# PCB_teensy.net
KiCad netlist of a schematic drawn in EAGLE
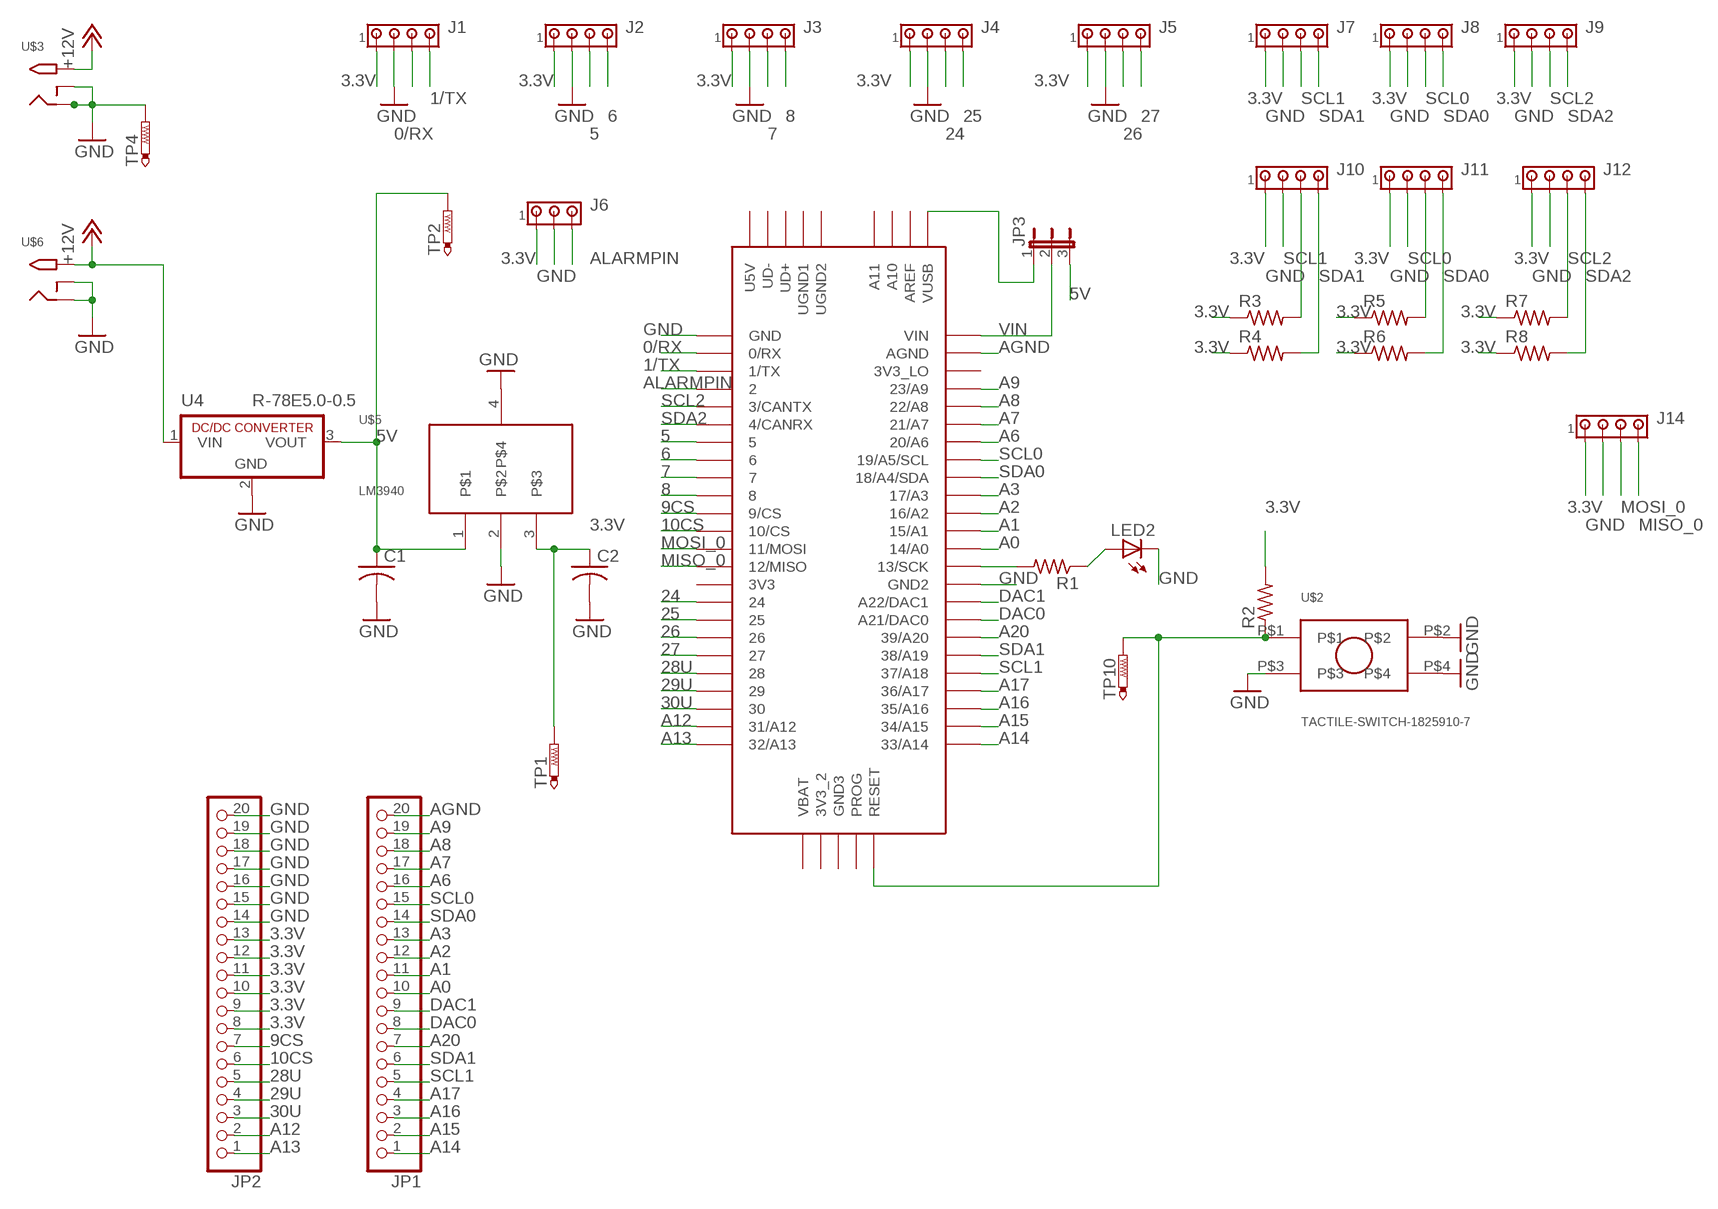
[diagram p0: schematic, sheet 1]

(export (version "E")
  (design (tool "Eeschema 10.0.6"))
  (components
    (comp (ref "C1")
      (value "C-USC0805")
      (footprint "eagle-import:C0805")
      (libsource (lib "eagle-import") (part "C-USC0805"))
    )
    (comp (ref "C2")
      (value "C-USC0805")
      (footprint "eagle-import:C0805")
      (libsource (lib "eagle-import") (part "C-USC0805"))
    )
    (comp (ref "J1")
      (value "MTA04-100")
      (footprint "eagle-import:10X04MTA")
      (libsource (lib "eagle-import") (part "MTA04-100"))
    )
    (comp (ref "J2")
      (value "MTA04-100")
      (footprint "eagle-import:10X04MTA")
      (libsource (lib "eagle-import") (part "MTA04-100"))
    )
    (comp (ref "J3")
      (value "MTA04-100")
      (footprint "eagle-import:10X04MTA")
      (libsource (lib "eagle-import") (part "MTA04-100"))
    )
    (comp (ref "J4")
      (value "MTA04-100")
      (footprint "eagle-import:10X04MTA")
      (libsource (lib "eagle-import") (part "MTA04-100"))
    )
    (comp (ref "J5")
      (value "MTA04-100")
      (footprint "eagle-import:10X04MTA")
      (libsource (lib "eagle-import") (part "MTA04-100"))
    )
    (comp (ref "J6")
      (value "MTA03-100")
      (footprint "eagle-import:10X03MTA")
      (libsource (lib "eagle-import") (part "MTA03-100"))
    )
    (comp (ref "J7")
      (value "MTA04-100")
      (footprint "eagle-import:10X04MTA")
      (libsource (lib "eagle-import") (part "MTA04-100"))
    )
    (comp (ref "J8")
      (value "MTA04-100")
      (footprint "eagle-import:10X04MTA")
      (libsource (lib "eagle-import") (part "MTA04-100"))
    )
    (comp (ref "J9")
      (value "MTA04-100")
      (footprint "eagle-import:10X04MTA")
      (libsource (lib "eagle-import") (part "MTA04-100"))
    )
    (comp (ref "J10")
      (value "MTA04-100")
      (footprint "eagle-import:10X04MTA")
      (libsource (lib "eagle-import") (part "MTA04-100"))
    )
    (comp (ref "J11")
      (value "MTA04-100")
      (footprint "eagle-import:10X04MTA")
      (libsource (lib "eagle-import") (part "MTA04-100"))
    )
    (comp (ref "J12")
      (value "MTA04-100")
      (footprint "eagle-import:10X04MTA")
      (libsource (lib "eagle-import") (part "MTA04-100"))
    )
    (comp (ref "J14")
      (value "MTA04-100")
      (footprint "eagle-import:10X04MTA")
      (libsource (lib "eagle-import") (part "MTA04-100"))
    )
    (comp (ref "JP1")
      (value "PINHD-1X20")
      (footprint "eagle-import:1X20")
      (libsource (lib "eagle-import") (part "PINHD-1X20"))
    )
    (comp (ref "JP2")
      (value "PINHD-1X20")
      (footprint "eagle-import:1X20")
      (libsource (lib "eagle-import") (part "PINHD-1X20"))
    )
    (comp (ref "JP3")
      (value "JP2W")
      (footprint "eagle-import:JP2W")
      (libsource (lib "eagle-import") (part "JP2W"))
    )
    (comp (ref "LED2")
      (value "LEDCHIP-LED0805")
      (footprint "eagle-import:CHIP-LED0805")
      (libsource (lib "eagle-import") (part "LEDCHIP-LED0805"))
    )
    (comp (ref "R1")
      (value "R-US_R0805")
      (footprint "eagle-import:R0805")
      (libsource (lib "eagle-import") (part "R-US_R0805"))
    )
    (comp (ref "R2")
      (value "R-US_R0805")
      (footprint "eagle-import:R0805")
      (libsource (lib "eagle-import") (part "R-US_R0805"))
    )
    (comp (ref "R3")
      (value "R-US_R0805")
      (footprint "eagle-import:R0805")
      (libsource (lib "eagle-import") (part "R-US_R0805"))
    )
    (comp (ref "R4")
      (value "R-US_R0805")
      (footprint "eagle-import:R0805")
      (libsource (lib "eagle-import") (part "R-US_R0805"))
    )
    (comp (ref "R5")
      (value "R-US_R0805")
      (footprint "eagle-import:R0805")
      (libsource (lib "eagle-import") (part "R-US_R0805"))
    )
    (comp (ref "R6")
      (value "R-US_R0805")
      (footprint "eagle-import:R0805")
      (libsource (lib "eagle-import") (part "R-US_R0805"))
    )
    (comp (ref "R7")
      (value "R-US_R0805")
      (footprint "eagle-import:R0805")
      (libsource (lib "eagle-import") (part "R-US_R0805"))
    )
    (comp (ref "R8")
      (value "R-US_R0805")
      (footprint "eagle-import:R0805")
      (libsource (lib "eagle-import") (part "R-US_R0805"))
    )
    (comp (ref "TP1")
      (value "PTR1B2,54")
      (footprint "eagle-import:B2,54")
      (libsource (lib "eagle-import") (part "PTR1B2,54"))
    )
    (comp (ref "TP2")
      (value "PTR1B2,54")
      (footprint "eagle-import:B2,54")
      (libsource (lib "eagle-import") (part "PTR1B2,54"))
    )
    (comp (ref "TP4")
      (value "PTR1B2,54")
      (footprint "eagle-import:B2,54")
      (libsource (lib "eagle-import") (part "PTR1B2,54"))
    )
    (comp (ref "TP10")
      (value "PTR1B2,54")
      (footprint "eagle-import:B2,54")
      (libsource (lib "eagle-import") (part "PTR1B2,54"))
    )
    (comp (ref "U$1")
      (value "TEENSY_3.5/3.6")
      (footprint "eagle-import:TEENSY_3.5_3.6")
      (libsource (lib "eagle-import") (part "TEENSY_3.5/3.6"))
    )
    (comp (ref "U$2")
      (value "TACTILE-SWITCH-1825910-7")
      (footprint "eagle-import:1825910-7")
      (libsource (lib "eagle-import") (part "TACTILE-SWITCH-1825910-7"))
    )
    (comp (ref "U$3")
      (value "2.1MMJACKTHM")
      (footprint "eagle-import:PJ-102A")
      (libsource (lib "eagle-import") (part "2.1MMJACKTHM"))
    )
    (comp (ref "U$5")
      (value "LM3940")
      (footprint "eagle-import:SOT223")
      (libsource (lib "eagle-import") (part "LM3940"))
    )
    (comp (ref "U$6")
      (value "2.1MMJACKTHM")
      (footprint "eagle-import:PJ-102A")
      (libsource (lib "eagle-import") (part "2.1MMJACKTHM"))
    )
    (comp (ref "U4")
      (value "R-78E5.0-0.5")
      (footprint "eagle-import:SIP3")
      (libsource (lib "eagle-import") (part "R-78E5.0-0.5"))
    )
  )
  (nets
    (net (code "1") (name "+12V") (class "Default")
      (node (ref "U$3") (pin "TIP") (pinfunction "TIP_TIP") (pintype "bidirectional"))
      (node (ref "U$6") (pin "TIP") (pinfunction "TIP_TIP") (pintype "bidirectional"))
      (node (ref "U4") (pin "1") (pinfunction "VIN_1") (pintype "passive"))
    )
    (net (code "2") (name "/0{slash}RX") (class "Default")
      (node (ref "J1") (pin "3") (pinfunction "3_3") (pintype "passive"))
      (node (ref "U$1") (pin "0/RX") (pinfunction "0/RX_0/RX") (pintype "bidirectional"))
    )
    (net (code "3") (name "/1{slash}TX") (class "Default")
      (node (ref "J1") (pin "4") (pinfunction "4_4") (pintype "passive"))
      (node (ref "U$1") (pin "1/TX") (pinfunction "1/TX_1/TX") (pintype "bidirectional"))
    )
    (net (code "4") (name "/3.3V") (class "Default")
      (node (ref "C2") (pin "1") (pinfunction "1_1") (pintype "passive"))
      (node (ref "J1") (pin "1") (pinfunction "1_1") (pintype "passive"))
      (node (ref "J10") (pin "1") (pinfunction "1_1") (pintype "passive"))
      (node (ref "J11") (pin "1") (pinfunction "1_1") (pintype "passive"))
      (node (ref "J12") (pin "1") (pinfunction "1_1") (pintype "passive"))
      (node (ref "J14") (pin "1") (pinfunction "1_1") (pintype "passive"))
      (node (ref "J2") (pin "1") (pinfunction "1_1") (pintype "passive"))
      (node (ref "J3") (pin "1") (pinfunction "1_1") (pintype "passive"))
      (node (ref "J4") (pin "1") (pinfunction "1_1") (pintype "passive"))
      (node (ref "J5") (pin "1") (pinfunction "1_1") (pintype "passive"))
      (node (ref "J6") (pin "1") (pinfunction "1_1") (pintype "passive"))
      (node (ref "J7") (pin "1") (pinfunction "1_1") (pintype "passive"))
      (node (ref "J8") (pin "1") (pinfunction "1_1") (pintype "passive"))
      (node (ref "J9") (pin "1") (pinfunction "1_1") (pintype "passive"))
      (node (ref "JP2") (pin "10") (pinfunction "10_10") (pintype "passive"))
      (node (ref "JP2") (pin "11") (pinfunction "11_11") (pintype "passive"))
      (node (ref "JP2") (pin "12") (pinfunction "12_12") (pintype "passive"))
      (node (ref "JP2") (pin "13") (pinfunction "13_13") (pintype "passive"))
      (node (ref "JP2") (pin "8") (pinfunction "8_8") (pintype "passive"))
      (node (ref "JP2") (pin "9") (pinfunction "9_9") (pintype "passive"))
      (node (ref "R2") (pin "2") (pinfunction "2_2") (pintype "passive"))
      (node (ref "R3") (pin "1") (pinfunction "1_1") (pintype "passive"))
      (node (ref "R4") (pin "1") (pinfunction "1_1") (pintype "passive"))
      (node (ref "R5") (pin "1") (pinfunction "1_1") (pintype "passive"))
      (node (ref "R6") (pin "1") (pinfunction "1_1") (pintype "passive"))
      (node (ref "R7") (pin "1") (pinfunction "1_1") (pintype "passive"))
      (node (ref "R8") (pin "1") (pinfunction "1_1") (pintype "passive"))
      (node (ref "TP1") (pin "TP") (pinfunction "TP_TP") (pintype "input"))
      (node (ref "U$5") (pin "3") (pinfunction "P$3_3") (pintype "output"))
    )
    (net (code "5") (name "/5") (class "Default")
      (node (ref "J2") (pin "3") (pinfunction "3_3") (pintype "passive"))
      (node (ref "U$1") (pin "5") (pinfunction "5_5") (pintype "bidirectional"))
    )
    (net (code "6") (name "/5V") (class "Default")
      (node (ref "C1") (pin "1") (pinfunction "1_1") (pintype "passive"))
      (node (ref "JP3") (pin "3") (pinfunction "3_3") (pintype "passive"))
      (node (ref "TP2") (pin "TP") (pinfunction "TP_TP") (pintype "input"))
      (node (ref "U$5") (pin "1") (pinfunction "P$1_1") (pintype "input"))
      (node (ref "U4") (pin "3") (pinfunction "VOUT_3") (pintype "passive"))
    )
    (net (code "7") (name "/6") (class "Default")
      (node (ref "J2") (pin "4") (pinfunction "4_4") (pintype "passive"))
      (node (ref "U$1") (pin "6") (pinfunction "6_6") (pintype "bidirectional"))
    )
    (net (code "8") (name "/7") (class "Default")
      (node (ref "J3") (pin "3") (pinfunction "3_3") (pintype "passive"))
      (node (ref "U$1") (pin "7") (pinfunction "7_7") (pintype "bidirectional"))
    )
    (net (code "9") (name "/8") (class "Default")
      (node (ref "J3") (pin "4") (pinfunction "4_4") (pintype "passive"))
      (node (ref "U$1") (pin "8") (pinfunction "8_8") (pintype "bidirectional"))
    )
    (net (code "10") (name "/9CS") (class "Default")
      (node (ref "JP2") (pin "7") (pinfunction "7_7") (pintype "passive"))
      (node (ref "U$1") (pin "9/CS") (pinfunction "9/CS_9/CS") (pintype "bidirectional"))
    )
    (net (code "11") (name "/10CS") (class "Default")
      (node (ref "JP2") (pin "6") (pinfunction "6_6") (pintype "passive"))
      (node (ref "U$1") (pin "10/CS") (pinfunction "10/CS_10/CS") (pintype "bidirectional"))
    )
    (net (code "12") (name "/24") (class "Default")
      (node (ref "J4") (pin "3") (pinfunction "3_3") (pintype "passive"))
      (node (ref "U$1") (pin "24") (pinfunction "24_24") (pintype "bidirectional"))
    )
    (net (code "13") (name "/25") (class "Default")
      (node (ref "J4") (pin "4") (pinfunction "4_4") (pintype "passive"))
      (node (ref "U$1") (pin "25") (pinfunction "25_25") (pintype "bidirectional"))
    )
    (net (code "14") (name "/26") (class "Default")
      (node (ref "J5") (pin "3") (pinfunction "3_3") (pintype "passive"))
      (node (ref "U$1") (pin "26") (pinfunction "26_26") (pintype "bidirectional"))
    )
    (net (code "15") (name "/27") (class "Default")
      (node (ref "J5") (pin "4") (pinfunction "4_4") (pintype "passive"))
      (node (ref "U$1") (pin "27") (pinfunction "27_27") (pintype "bidirectional"))
    )
    (net (code "16") (name "/28U") (class "Default")
      (node (ref "JP2") (pin "5") (pinfunction "5_5") (pintype "passive"))
      (node (ref "U$1") (pin "28") (pinfunction "28_28") (pintype "bidirectional"))
    )
    (net (code "17") (name "/29U") (class "Default")
      (node (ref "JP2") (pin "4") (pinfunction "4_4") (pintype "passive"))
      (node (ref "U$1") (pin "29") (pinfunction "29_29") (pintype "bidirectional"))
    )
    (net (code "18") (name "/30U") (class "Default")
      (node (ref "JP2") (pin "3") (pinfunction "3_3") (pintype "passive"))
      (node (ref "U$1") (pin "30") (pinfunction "30_30") (pintype "bidirectional"))
    )
    (net (code "19") (name "/A0") (class "Default")
      (node (ref "JP1") (pin "10") (pinfunction "10_10") (pintype "passive"))
      (node (ref "U$1") (pin "14/A0") (pinfunction "14/A0_14/A0") (pintype "bidirectional"))
    )
    (net (code "20") (name "/A1") (class "Default")
      (node (ref "JP1") (pin "11") (pinfunction "11_11") (pintype "passive"))
      (node (ref "U$1") (pin "15/A1") (pinfunction "15/A1_15/A1") (pintype "bidirectional"))
    )
    (net (code "21") (name "/A2") (class "Default")
      (node (ref "JP1") (pin "12") (pinfunction "12_12") (pintype "passive"))
      (node (ref "U$1") (pin "16/A2") (pinfunction "16/A2_16/A2") (pintype "bidirectional"))
    )
    (net (code "22") (name "/A3") (class "Default")
      (node (ref "JP1") (pin "13") (pinfunction "13_13") (pintype "passive"))
      (node (ref "U$1") (pin "17/A3") (pinfunction "17/A3_17/A3") (pintype "bidirectional"))
    )
    (net (code "23") (name "/A6") (class "Default")
      (node (ref "JP1") (pin "16") (pinfunction "16_16") (pintype "passive"))
      (node (ref "U$1") (pin "20/A6") (pinfunction "20/A6_20/A6") (pintype "bidirectional"))
    )
    (net (code "24") (name "/A7") (class "Default")
      (node (ref "JP1") (pin "17") (pinfunction "17_17") (pintype "passive"))
      (node (ref "U$1") (pin "21/A7") (pinfunction "21/A7_21/A7") (pintype "bidirectional"))
    )
    (net (code "25") (name "/A8") (class "Default")
      (node (ref "JP1") (pin "18") (pinfunction "18_18") (pintype "passive"))
      (node (ref "U$1") (pin "22/A8") (pinfunction "22/A8_22/A8") (pintype "bidirectional"))
    )
    (net (code "26") (name "/A9") (class "Default")
      (node (ref "JP1") (pin "19") (pinfunction "19_19") (pintype "passive"))
      (node (ref "U$1") (pin "23/A9") (pinfunction "23/A9_23/A9") (pintype "bidirectional"))
    )
    (net (code "27") (name "/A12") (class "Default")
      (node (ref "JP2") (pin "2") (pinfunction "2_2") (pintype "passive"))
      (node (ref "U$1") (pin "31/A12") (pinfunction "31/A12_31/A12") (pintype "bidirectional"))
    )
    (net (code "28") (name "/A13") (class "Default")
      (node (ref "JP2") (pin "1") (pinfunction "1_1") (pintype "passive"))
      (node (ref "U$1") (pin "32/A13") (pinfunction "32/A13_32/A13") (pintype "bidirectional"))
    )
    (net (code "29") (name "/A14") (class "Default")
      (node (ref "JP1") (pin "1") (pinfunction "1_1") (pintype "passive"))
      (node (ref "U$1") (pin "33/A14") (pinfunction "33/A14_33/A14") (pintype "bidirectional"))
    )
    (net (code "30") (name "/A15") (class "Default")
      (node (ref "JP1") (pin "2") (pinfunction "2_2") (pintype "passive"))
      (node (ref "U$1") (pin "34/A15") (pinfunction "34/A15_34/A15") (pintype "bidirectional"))
    )
    (net (code "31") (name "/A16") (class "Default")
      (node (ref "JP1") (pin "3") (pinfunction "3_3") (pintype "passive"))
      (node (ref "U$1") (pin "35/A16") (pinfunction "35/A16_35/A16") (pintype "bidirectional"))
    )
    (net (code "32") (name "/A17") (class "Default")
      (node (ref "JP1") (pin "4") (pinfunction "4_4") (pintype "passive"))
      (node (ref "U$1") (pin "36/A17") (pinfunction "36/A17_36/A17") (pintype "bidirectional"))
    )
    (net (code "33") (name "/A20") (class "Default")
      (node (ref "JP1") (pin "7") (pinfunction "7_7") (pintype "passive"))
      (node (ref "U$1") (pin "39/A20") (pinfunction "39/A20_39/A20") (pintype "bidirectional"))
    )
    (net (code "34") (name "/AGND") (class "Default")
      (node (ref "JP1") (pin "20") (pinfunction "20_20") (pintype "passive"))
      (node (ref "U$1") (pin "AGND") (pinfunction "AGND_AGND") (pintype "bidirectional"))
    )
    (net (code "35") (name "/ALARMPIN") (class "Default")
      (node (ref "J6") (pin "3") (pinfunction "3_3") (pintype "passive"))
      (node (ref "U$1") (pin "2") (pinfunction "2_2") (pintype "bidirectional"))
    )
    (net (code "36") (name "/DAC0") (class "Default")
      (node (ref "JP1") (pin "8") (pinfunction "8_8") (pintype "passive"))
      (node (ref "U$1") (pin "21/DAC0") (pinfunction "A21/DAC0_21/DAC0") (pintype "bidirectional"))
    )
    (net (code "37") (name "/DAC1") (class "Default")
      (node (ref "JP1") (pin "9") (pinfunction "9_9") (pintype "passive"))
      (node (ref "U$1") (pin "A22/DAC1") (pinfunction "A22/DAC1_A22/DAC1") (pintype "bidirectional"))
    )
    (net (code "38") (name "/MISO_0") (class "Default")
      (node (ref "J14") (pin "4") (pinfunction "4_4") (pintype "passive"))
      (node (ref "U$1") (pin "12/MISO") (pinfunction "12/MISO_12/MISO") (pintype "bidirectional"))
    )
    (net (code "39") (name "/MOSI_0") (class "Default")
      (node (ref "J14") (pin "3") (pinfunction "3_3") (pintype "passive"))
      (node (ref "U$1") (pin "11/MOSI") (pinfunction "11/MOSI_11/MOSI") (pintype "bidirectional"))
    )
    (net (code "40") (name "/SCL0") (class "Default")
      (node (ref "J11") (pin "3") (pinfunction "3_3") (pintype "passive"))
      (node (ref "J8") (pin "3") (pinfunction "3_3") (pintype "passive"))
      (node (ref "JP1") (pin "15") (pinfunction "15_15") (pintype "passive"))
      (node (ref "R5") (pin "2") (pinfunction "2_2") (pintype "passive"))
      (node (ref "U$1") (pin "19/A5/SCL") (pinfunction "19/A5/SCL_19/A5/SCL") (pintype "bidirectional"))
    )
    (net (code "41") (name "/SCL1") (class "Default")
      (node (ref "J10") (pin "3") (pinfunction "3_3") (pintype "passive"))
      (node (ref "J7") (pin "3") (pinfunction "3_3") (pintype "passive"))
      (node (ref "JP1") (pin "5") (pinfunction "5_5") (pintype "passive"))
      (node (ref "R3") (pin "2") (pinfunction "2_2") (pintype "passive"))
      (node (ref "U$1") (pin "37/A18") (pinfunction "37/A18_37/A18") (pintype "bidirectional"))
    )
    (net (code "42") (name "/SCL2") (class "Default")
      (node (ref "J12") (pin "3") (pinfunction "3_3") (pintype "passive"))
      (node (ref "J9") (pin "3") (pinfunction "3_3") (pintype "passive"))
      (node (ref "R7") (pin "2") (pinfunction "2_2") (pintype "passive"))
      (node (ref "U$1") (pin "3/CANTX") (pinfunction "3/CANTX_3/CANTX") (pintype "bidirectional"))
    )
    (net (code "43") (name "/SDA0") (class "Default")
      (node (ref "J11") (pin "4") (pinfunction "4_4") (pintype "passive"))
      (node (ref "J8") (pin "4") (pinfunction "4_4") (pintype "passive"))
      (node (ref "JP1") (pin "14") (pinfunction "14_14") (pintype "passive"))
      (node (ref "R6") (pin "2") (pinfunction "2_2") (pintype "passive"))
      (node (ref "U$1") (pin "18/A4/SDA") (pinfunction "18/A4/SDA_18/A4/SDA") (pintype "bidirectional"))
    )
    (net (code "44") (name "/SDA1") (class "Default")
      (node (ref "J10") (pin "4") (pinfunction "4_4") (pintype "passive"))
      (node (ref "J7") (pin "4") (pinfunction "4_4") (pintype "passive"))
      (node (ref "JP1") (pin "6") (pinfunction "6_6") (pintype "passive"))
      (node (ref "R4") (pin "2") (pinfunction "2_2") (pintype "passive"))
      (node (ref "U$1") (pin "38/A19") (pinfunction "38/A19_38/A19") (pintype "bidirectional"))
    )
    (net (code "45") (name "/SDA2") (class "Default")
      (node (ref "J12") (pin "4") (pinfunction "4_4") (pintype "passive"))
      (node (ref "J9") (pin "4") (pinfunction "4_4") (pintype "passive"))
      (node (ref "R8") (pin "2") (pinfunction "2_2") (pintype "passive"))
      (node (ref "U$1") (pin "4/CANRX") (pinfunction "4/CANRX_4/CANRX") (pintype "bidirectional"))
    )
    (net (code "46") (name "/VIN") (class "Default")
      (node (ref "JP3") (pin "2") (pinfunction "2_2") (pintype "passive"))
      (node (ref "U$1") (pin "VIN") (pinfunction "VIN_VIN") (pintype "bidirectional"))
    )
    (net (code "47") (name "GND") (class "Default")
      (node (ref "C1") (pin "2") (pinfunction "2_2") (pintype "passive"))
      (node (ref "C2") (pin "2") (pinfunction "2_2") (pintype "passive"))
      (node (ref "J1") (pin "2") (pinfunction "2_2") (pintype "passive"))
      (node (ref "J10") (pin "2") (pinfunction "2_2") (pintype "passive"))
      (node (ref "J11") (pin "2") (pinfunction "2_2") (pintype "passive"))
      (node (ref "J12") (pin "2") (pinfunction "2_2") (pintype "passive"))
      (node (ref "J14") (pin "2") (pinfunction "2_2") (pintype "passive"))
      (node (ref "J2") (pin "2") (pinfunction "2_2") (pintype "passive"))
      (node (ref "J3") (pin "2") (pinfunction "2_2") (pintype "passive"))
      (node (ref "J4") (pin "2") (pinfunction "2_2") (pintype "passive"))
      (node (ref "J5") (pin "2") (pinfunction "2_2") (pintype "passive"))
      (node (ref "J6") (pin "2") (pinfunction "2_2") (pintype "passive"))
      (node (ref "J7") (pin "2") (pinfunction "2_2") (pintype "passive"))
      (node (ref "J8") (pin "2") (pinfunction "2_2") (pintype "passive"))
      (node (ref "J9") (pin "2") (pinfunction "2_2") (pintype "passive"))
      (node (ref "JP2") (pin "14") (pinfunction "14_14") (pintype "passive"))
      (node (ref "JP2") (pin "15") (pinfunction "15_15") (pintype "passive"))
      (node (ref "JP2") (pin "16") (pinfunction "16_16") (pintype "passive"))
      (node (ref "JP2") (pin "17") (pinfunction "17_17") (pintype "passive"))
      (node (ref "JP2") (pin "18") (pinfunction "18_18") (pintype "passive"))
      (node (ref "JP2") (pin "19") (pinfunction "19_19") (pintype "passive"))
      (node (ref "JP2") (pin "20") (pinfunction "20_20") (pintype "passive"))
      (node (ref "LED2") (pin "C") (pinfunction "C_C") (pintype "passive"))
      (node (ref "TP4") (pin "TP") (pinfunction "TP_TP") (pintype "input"))
      (node (ref "U$1") (pin "GND") (pinfunction "GND_GND") (pintype "bidirectional"))
      (node (ref "U$1") (pin "GND2") (pinfunction "GND2_GND2") (pintype "bidirectional"))
      (node (ref "U$2") (pin "P$2") (pinfunction "P$2_P$2") (pintype "bidirectional"))
      (node (ref "U$2") (pin "P$3") (pinfunction "P$3_P$3") (pintype "bidirectional"))
      (node (ref "U$2") (pin "P$4") (pinfunction "P$4_P$4") (pintype "bidirectional"))
      (node (ref "U$3") (pin "RING") (pinfunction "RING_RING") (pintype "bidirectional"))
      (node (ref "U$3") (pin "RING_SW") (pinfunction "RING_SW_RING_SW") (pintype "bidirectional"))
      (node (ref "U$5") (pin "2") (pinfunction "P$2_2") (pintype "bidirectional"))
      (node (ref "U$5") (pin "4") (pinfunction "P$4_4") (pintype "bidirectional"))
      (node (ref "U$6") (pin "RING") (pinfunction "RING_RING") (pintype "bidirectional"))
      (node (ref "U$6") (pin "RING_SW") (pinfunction "RING_SW_RING_SW") (pintype "bidirectional"))
      (node (ref "U4") (pin "2") (pinfunction "GND_2") (pintype "passive"))
    )
    (net (code "48") (name "Net-(JP3-Pad1)") (class "Default")
      (node (ref "JP3") (pin "1") (pinfunction "1_1") (pintype "passive"))
      (node (ref "U$1") (pin "VUSB") (pinfunction "VUSB_VUSB") (pintype "bidirectional"))
    )
    (net (code "49") (name "Net-(LED2-PadA)") (class "Default")
      (node (ref "LED2") (pin "A") (pinfunction "A_A") (pintype "passive"))
      (node (ref "R1") (pin "1") (pinfunction "1_1") (pintype "passive"))
    )
    (net (code "50") (name "Net-(R1-Pad2)") (class "Default")
      (node (ref "R1") (pin "2") (pinfunction "2_2") (pintype "passive"))
      (node (ref "U$1") (pin "13/SCK") (pinfunction "13/SCK_13/SCK") (pintype "bidirectional"))
    )
    (net (code "51") (name "Net-(R2-Pad1)") (class "Default")
      (node (ref "R2") (pin "1") (pinfunction "1_1") (pintype "passive"))
      (node (ref "TP10") (pin "TP") (pinfunction "TP_TP") (pintype "input"))
      (node (ref "U$1") (pin "RESET") (pinfunction "RESET_RESET") (pintype "bidirectional"))
      (node (ref "U$2") (pin "P$1") (pinfunction "P$1_P$1") (pintype "bidirectional"))
    )
    (net (code "52") (name "unconnected-(U$1-Pad3V3)") (class "Default")
      (node (ref "U$1") (pin "3V3") (pinfunction "3V3_3V3") (pintype "bidirectional"))
    )
    (net (code "53") (name "unconnected-(U$1-Pad3V3_2)") (class "Default")
      (node (ref "U$1") (pin "3V3_2") (pinfunction "3V3_2_3V3_2") (pintype "bidirectional"))
    )
    (net (code "54") (name "unconnected-(U$1-Pad3V3_LO)") (class "Default")
      (node (ref "U$1") (pin "3V3_LO") (pinfunction "3V3_LO_3V3_LO") (pintype "bidirectional"))
    )
    (net (code "55") (name "unconnected-(U$1-PadA10)") (class "Default")
      (node (ref "U$1") (pin "A10") (pinfunction "A10_A10") (pintype "bidirectional"))
    )
    (net (code "56") (name "unconnected-(U$1-PadA11)") (class "Default")
      (node (ref "U$1") (pin "A11") (pinfunction "A11_A11") (pintype "bidirectional"))
    )
    (net (code "57") (name "unconnected-(U$1-PadAREF)") (class "Default")
      (node (ref "U$1") (pin "AREF") (pinfunction "AREF_AREF") (pintype "bidirectional"))
    )
    (net (code "58") (name "unconnected-(U$1-PadGND3)") (class "Default")
      (node (ref "U$1") (pin "GND3") (pinfunction "GND3_GND3") (pintype "bidirectional"))
    )
    (net (code "59") (name "unconnected-(U$1-PadPROG)") (class "Default")
      (node (ref "U$1") (pin "PROG") (pinfunction "PROG_PROG") (pintype "bidirectional"))
    )
    (net (code "60") (name "unconnected-(U$1-PadU5V)") (class "Default")
      (node (ref "U$1") (pin "U5V") (pinfunction "U5V_U5V") (pintype "bidirectional"))
    )
    (net (code "61") (name "unconnected-(U$1-PadUD+)") (class "Default")
      (node (ref "U$1") (pin "UD+") (pinfunction "UD+_UD+") (pintype "bidirectional"))
    )
    (net (code "62") (name "unconnected-(U$1-PadUD-)") (class "Default")
      (node (ref "U$1") (pin "UD-") (pinfunction "UD-_UD-") (pintype "bidirectional"))
    )
    (net (code "63") (name "unconnected-(U$1-PadUGND1)") (class "Default")
      (node (ref "U$1") (pin "UGND1") (pinfunction "UGND1_UGND1") (pintype "bidirectional"))
    )
    (net (code "64") (name "unconnected-(U$1-PadUGND2)") (class "Default")
      (node (ref "U$1") (pin "UGND2") (pinfunction "UGND2_UGND2") (pintype "bidirectional"))
    )
    (net (code "65") (name "unconnected-(U$1-PadVBAT)") (class "Default")
      (node (ref "U$1") (pin "VBAT") (pinfunction "VBAT_VBAT") (pintype "bidirectional"))
    )
  )
)
